# Carte_elec.net
KiCad netlist of a schematic drawn in EAGLE
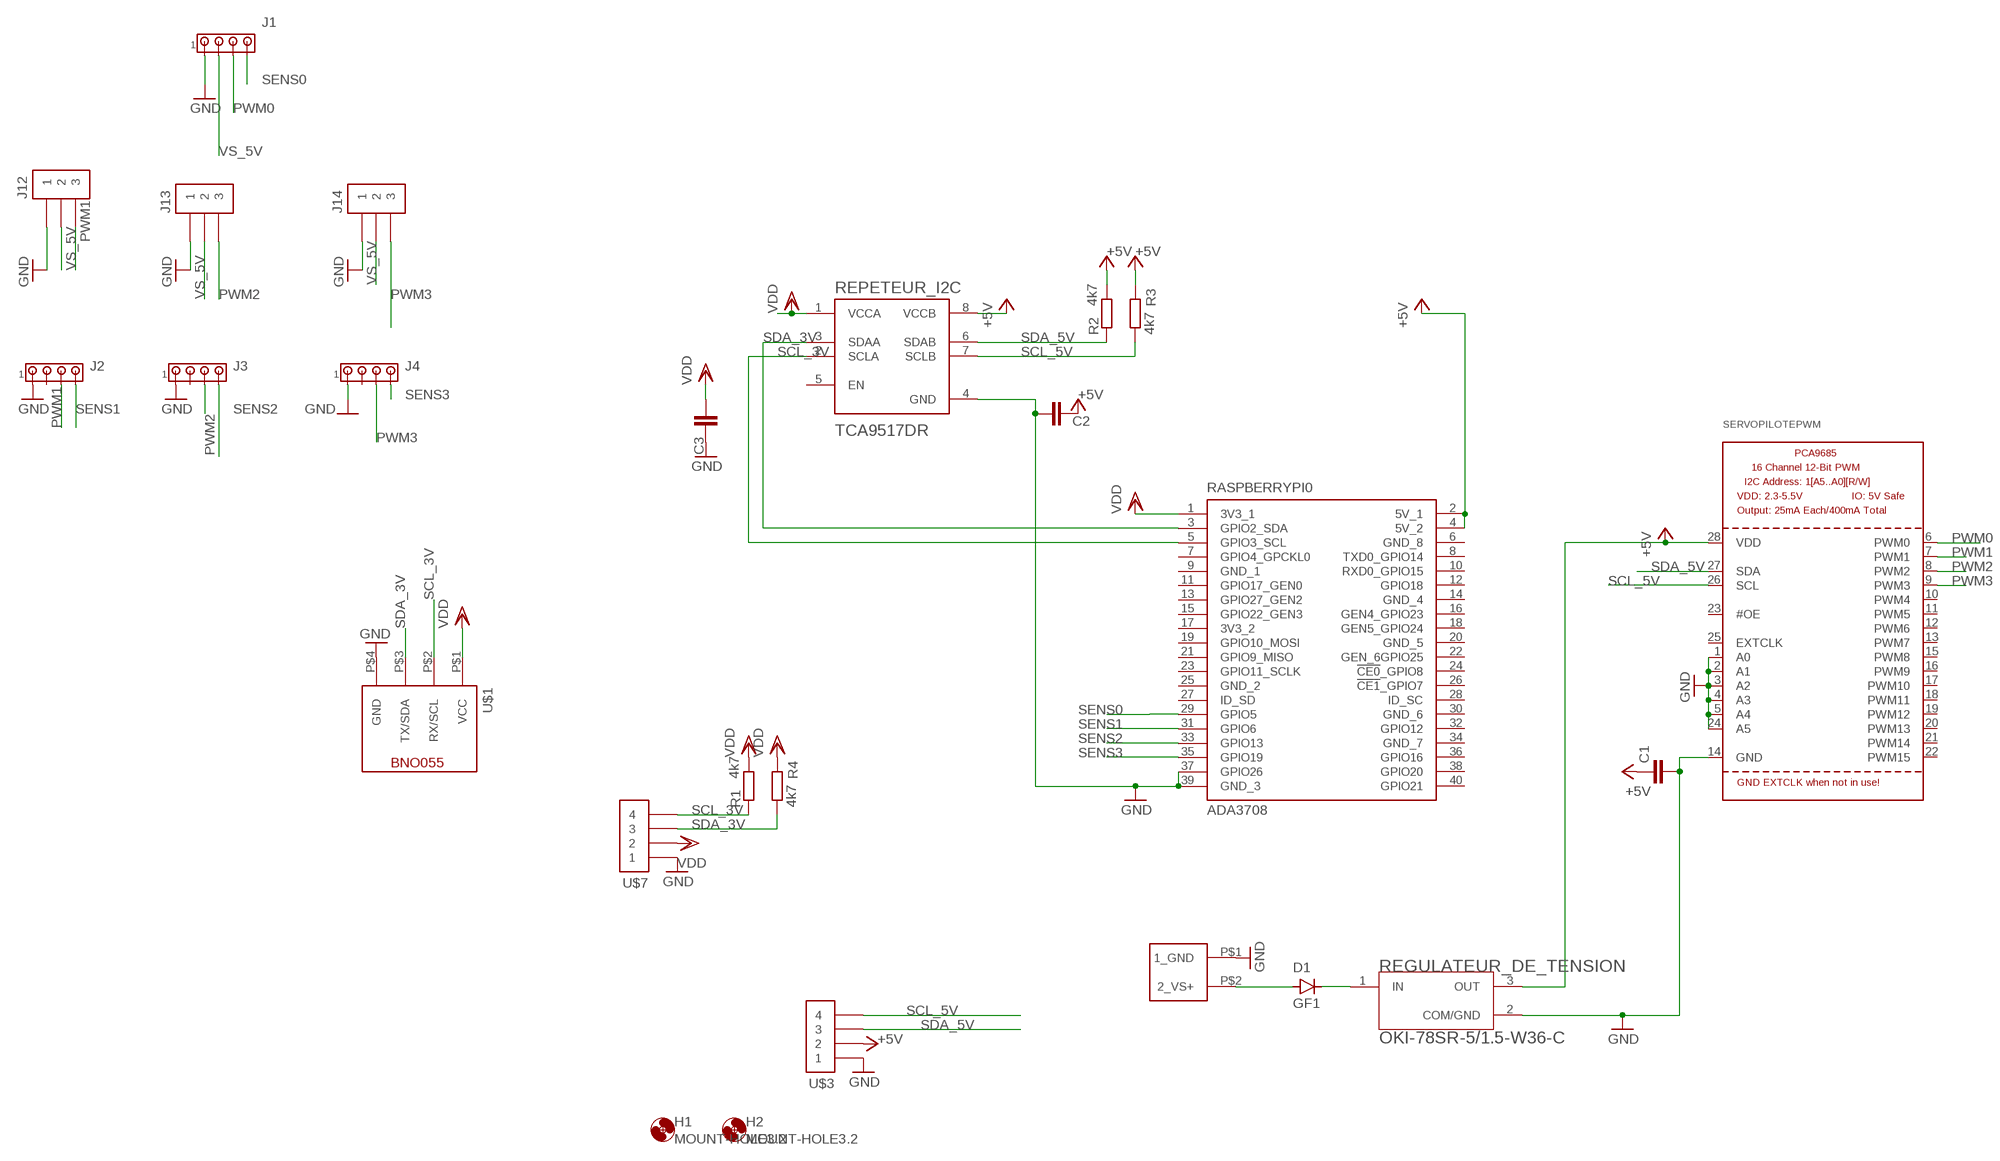
[diagram p0: schematic, sheet 1]

(export (version "E")
  (design (tool "Eeschema 10.0.6"))
  (components
    (comp (ref "C1")
      (value "C-EUC1206")
      (footprint "eagle-import:C1206")
      (libsource (lib "eagle-import") (part "C-EUC1206"))
    )
    (comp (ref "C2")
      (value "C-EUC1206")
      (footprint "eagle-import:C1206")
      (libsource (lib "eagle-import") (part "C-EUC1206"))
    )
    (comp (ref "C3")
      (value "C-EUC1206")
      (footprint "eagle-import:C1206")
      (libsource (lib "eagle-import") (part "C-EUC1206"))
    )
    (comp (ref "D1")
      (value "GF1")
      (footprint "eagle-import:SMA-DO214AC")
      (libsource (lib "eagle-import") (part "GF1"))
    )
    (comp (ref "H1")
      (value "MOUNT-HOLE3.2")
      (footprint "eagle-import:3,2")
      (libsource (lib "eagle-import") (part "MOUNT-HOLE3.2"))
    )
    (comp (ref "H2")
      (value "MOUNT-HOLE3.2")
      (footprint "eagle-import:3,2")
      (libsource (lib "eagle-import") (part "MOUNT-HOLE3.2"))
    )
    (comp (ref "J1")
      (value "MTA04-100")
      (footprint "eagle-import:10X04MTA")
      (libsource (lib "eagle-import") (part "MTA04-100"))
    )
    (comp (ref "J2")
      (value "MTA04-100")
      (footprint "eagle-import:10X04MTA")
      (libsource (lib "eagle-import") (part "MTA04-100"))
    )
    (comp (ref "J3")
      (value "MTA04-100")
      (footprint "eagle-import:10X04MTA")
      (libsource (lib "eagle-import") (part "MTA04-100"))
    )
    (comp (ref "J4")
      (value "MTA04-100")
      (footprint "eagle-import:10X04MTA")
      (libsource (lib "eagle-import") (part "MTA04-100"))
    )
    (comp (ref "J12")
      (value "CAVALIER_3")
      (footprint "eagle-import:CAVALIER_3")
      (libsource (lib "eagle-import") (part "CAVALIER_3"))
    )
    (comp (ref "J13")
      (value "CAVALIER_3")
      (footprint "eagle-import:CAVALIER_3")
      (libsource (lib "eagle-import") (part "CAVALIER_3"))
    )
    (comp (ref "J14")
      (value "CAVALIER_3")
      (footprint "eagle-import:CAVALIER_3")
      (libsource (lib "eagle-import") (part "CAVALIER_3"))
    )
    (comp (ref "R1")
      (value "4k7")
      (footprint "eagle-import:R1206")
      (libsource (lib "eagle-import") (part "R-EU_R1206"))
    )
    (comp (ref "R2")
      (value "4k7")
      (footprint "eagle-import:R1206")
      (libsource (lib "eagle-import") (part "R-EU_R1206"))
    )
    (comp (ref "R3")
      (value "4k7")
      (footprint "eagle-import:R1206")
      (libsource (lib "eagle-import") (part "R-EU_R1206"))
    )
    (comp (ref "R4")
      (value "4k7")
      (footprint "eagle-import:R1206")
      (libsource (lib "eagle-import") (part "R-EU_R1206"))
    )
    (comp (ref "RASPBERRYPI0")
      (value "ADA3708")
      (footprint "eagle-import:MODULE_ADA3708")
      (fields (field (name "MF") "Adafruit Industries"))
      (libsource (lib "eagle-import") (part "ADA3708"))
    )
    (comp (ref "REGULATEUR_DE_TENSION")
      (value "OKI-78SR-5/1.5-W36-C")
      (footprint "eagle-import:CONV_OKI-78SR-5_1.5-W36-C")
      (fields (field (name "MF") "Murata Power Solutions"))
      (libsource (lib "eagle-import") (part "OKI-78SR-5/1.5-W36-C"))
    )
    (comp (ref "REPETEUR_I2C")
      (value "TCA9517DR")
      (footprint "eagle-import:SOIC127P599X175-8N")
      (fields (field (name "MF") "Texas Instruments"))
      (libsource (lib "eagle-import") (part "TCA9517DR"))
    )
    (comp (ref "SERVOPILOTEPWM")
      (value "PCA9685")
      (footprint "eagle-import:TSSOP28")
      (libsource (lib "eagle-import") (part "PCA9685"))
    )
    (comp (ref "U$1")
      (value "MODULE_BNO055")
      (footprint "eagle-import:MODULE_BNO055")
      (libsource (lib "eagle-import") (part "MODULE_BNO055"))
    )
    (comp (ref "U$2")
      (value "CONN_ALIM")
      (footprint "eagle-import:CONN_ALIM")
      (libsource (lib "eagle-import") (part "CONN_ALIM"))
    )
    (comp (ref "U$3")
      (value "MOLEX_4_DROIT")
      (footprint "eagle-import:MOLEX_4_DROIT")
      (libsource (lib "eagle-import") (part "MOLEX_4_DROIT"))
    )
    (comp (ref "U$7")
      (value "MOLEX_4_DROIT")
      (footprint "eagle-import:MOLEX_4_DROIT")
      (libsource (lib "eagle-import") (part "MOLEX_4_DROIT"))
    )
  )
  (nets
    (net (code "1") (name "+5V") (class "Default")
      (node (ref "C1") (pin "1") (pinfunction "1_1") (pintype "passive"))
      (node (ref "C2") (pin "1") (pinfunction "1_1") (pintype "passive"))
      (node (ref "R2") (pin "2") (pinfunction "2_2") (pintype "passive"))
      (node (ref "R3") (pin "2") (pinfunction "2_2") (pintype "passive"))
      (node (ref "RASPBERRYPI0") (pin "2") (pinfunction "5V_1_2") (pintype "power_in"))
      (node (ref "RASPBERRYPI0") (pin "4") (pinfunction "5V_2_4") (pintype "power_in"))
      (node (ref "REGULATEUR_DE_TENSION") (pin "3") (pinfunction "OUT_3") (pintype "output"))
      (node (ref "REPETEUR_I2C") (pin "8") (pinfunction "VCCB_8") (pintype "power_in"))
      (node (ref "SERVOPILOTEPWM") (pin "28") (pinfunction "VDD_28") (pintype "power_in"))
      (node (ref "U$3") (pin "P$2") (pinfunction "2_P$2") (pintype "bidirectional"))
    )
    (net (code "2") (name "/3V3_2") (class "Default")
      (node (ref "RASPBERRYPI0") (pin "17") (pinfunction "3V3_2_17") (pintype "power_in"))
    )
    (net (code "3") (name "/GND_1") (class "Default")
      (node (ref "RASPBERRYPI0") (pin "9") (pinfunction "GND_1_9") (pintype "power_in"))
    )
    (net (code "4") (name "/GND_2") (class "Default")
      (node (ref "RASPBERRYPI0") (pin "25") (pinfunction "GND_2_25") (pintype "power_in"))
    )
    (net (code "5") (name "/GND_4") (class "Default")
      (node (ref "RASPBERRYPI0") (pin "14") (pinfunction "GND_4_14") (pintype "power_in"))
    )
    (net (code "6") (name "/GND_5") (class "Default")
      (node (ref "RASPBERRYPI0") (pin "20") (pinfunction "GND_5_20") (pintype "power_in"))
    )
    (net (code "7") (name "/GND_6") (class "Default")
      (node (ref "RASPBERRYPI0") (pin "30") (pinfunction "GND_6_30") (pintype "power_in"))
    )
    (net (code "8") (name "/GND_7") (class "Default")
      (node (ref "RASPBERRYPI0") (pin "34") (pinfunction "GND_7_34") (pintype "power_in"))
    )
    (net (code "9") (name "/GND_8") (class "Default")
      (node (ref "RASPBERRYPI0") (pin "6") (pinfunction "GND_8_6") (pintype "power_in"))
    )
    (net (code "10") (name "/PWM0") (class "Default")
      (node (ref "J1") (pin "3") (pinfunction "3_3") (pintype "passive"))
      (node (ref "SERVOPILOTEPWM") (pin "6") (pinfunction "PWM0_6") (pintype "output"))
    )
    (net (code "11") (name "/PWM1") (class "Default")
      (node (ref "J12") (pin "P$3") (pinfunction "3_P$3") (pintype "bidirectional"))
      (node (ref "J2") (pin "3") (pinfunction "3_3") (pintype "passive"))
      (node (ref "SERVOPILOTEPWM") (pin "7") (pinfunction "PWM1_7") (pintype "output"))
    )
    (net (code "12") (name "/PWM2") (class "Default")
      (node (ref "J13") (pin "P$3") (pinfunction "3_P$3") (pintype "bidirectional"))
      (node (ref "J3") (pin "3") (pinfunction "3_3") (pintype "passive"))
      (node (ref "SERVOPILOTEPWM") (pin "8") (pinfunction "PWM2_8") (pintype "output"))
    )
    (net (code "13") (name "/PWM3") (class "Default")
      (node (ref "J14") (pin "P$3") (pinfunction "3_P$3") (pintype "bidirectional"))
      (node (ref "J4") (pin "3") (pinfunction "3_3") (pintype "passive"))
      (node (ref "SERVOPILOTEPWM") (pin "9") (pinfunction "PWM3_9") (pintype "output"))
    )
    (net (code "14") (name "/SCL_3V") (class "Default")
      (node (ref "R1") (pin "1") (pinfunction "1_1") (pintype "passive"))
      (node (ref "RASPBERRYPI0") (pin "5") (pinfunction "GPIO3_SCL_5") (pintype "bidirectional"))
      (node (ref "REPETEUR_I2C") (pin "2") (pinfunction "SCLA_2") (pintype "bidirectional"))
      (node (ref "U$1") (pin "P$2") (pinfunction "RX/SCL_P$2") (pintype "bidirectional"))
      (node (ref "U$7") (pin "P$4") (pinfunction "4_P$4") (pintype "bidirectional"))
    )
    (net (code "15") (name "/SCL_5V") (class "Default")
      (node (ref "R3") (pin "1") (pinfunction "1_1") (pintype "passive"))
      (node (ref "REPETEUR_I2C") (pin "7") (pinfunction "SCLB_7") (pintype "bidirectional"))
      (node (ref "SERVOPILOTEPWM") (pin "26") (pinfunction "SCL_26") (pintype "bidirectional"))
      (node (ref "U$3") (pin "P$4") (pinfunction "4_P$4") (pintype "bidirectional"))
    )
    (net (code "16") (name "/SDA_3V") (class "Default")
      (node (ref "R4") (pin "1") (pinfunction "1_1") (pintype "passive"))
      (node (ref "RASPBERRYPI0") (pin "3") (pinfunction "GPIO2_SDA_3") (pintype "bidirectional"))
      (node (ref "REPETEUR_I2C") (pin "3") (pinfunction "SDAA_3") (pintype "bidirectional"))
      (node (ref "U$1") (pin "P$3") (pinfunction "TX/SDA_P$3") (pintype "bidirectional"))
      (node (ref "U$7") (pin "P$3") (pinfunction "3_P$3") (pintype "bidirectional"))
    )
    (net (code "17") (name "/SDA_5V") (class "Default")
      (node (ref "R2") (pin "1") (pinfunction "1_1") (pintype "passive"))
      (node (ref "REPETEUR_I2C") (pin "6") (pinfunction "SDAB_6") (pintype "bidirectional"))
      (node (ref "SERVOPILOTEPWM") (pin "27") (pinfunction "SDA_27") (pintype "bidirectional"))
      (node (ref "U$3") (pin "P$3") (pinfunction "3_P$3") (pintype "bidirectional"))
    )
    (net (code "18") (name "/SENS0") (class "Default")
      (node (ref "J1") (pin "4") (pinfunction "4_4") (pintype "passive"))
      (node (ref "RASPBERRYPI0") (pin "29") (pinfunction "GPIO5_29") (pintype "bidirectional"))
    )
    (net (code "19") (name "/SENS1") (class "Default")
      (node (ref "J2") (pin "4") (pinfunction "4_4") (pintype "passive"))
      (node (ref "RASPBERRYPI0") (pin "31") (pinfunction "GPIO6_31") (pintype "bidirectional"))
    )
    (net (code "20") (name "/SENS2") (class "Default")
      (node (ref "J3") (pin "4") (pinfunction "4_4") (pintype "passive"))
      (node (ref "RASPBERRYPI0") (pin "33") (pinfunction "GPIO13_33") (pintype "bidirectional"))
    )
    (net (code "21") (name "/SENS3") (class "Default")
      (node (ref "J4") (pin "4") (pinfunction "4_4") (pintype "passive"))
      (node (ref "RASPBERRYPI0") (pin "35") (pinfunction "GPIO19_35") (pintype "bidirectional"))
    )
    (net (code "22") (name "/VS_5V") (class "Default")
      (node (ref "J1") (pin "2") (pinfunction "2_2") (pintype "passive"))
      (node (ref "J12") (pin "P$2") (pinfunction "2_P$2") (pintype "bidirectional"))
      (node (ref "J14") (pin "P$2") (pinfunction "2_P$2") (pintype "bidirectional"))
    )
    (net (code "23") (name "GND") (class "Default")
      (node (ref "C1") (pin "2") (pinfunction "2_2") (pintype "passive"))
      (node (ref "C2") (pin "2") (pinfunction "2_2") (pintype "passive"))
      (node (ref "C3") (pin "1") (pinfunction "1_1") (pintype "passive"))
      (node (ref "J1") (pin "1") (pinfunction "1_1") (pintype "passive"))
      (node (ref "J12") (pin "P$1") (pinfunction "1_P$1") (pintype "bidirectional"))
      (node (ref "J13") (pin "P$1") (pinfunction "1_P$1") (pintype "bidirectional"))
      (node (ref "J14") (pin "P$1") (pinfunction "1_P$1") (pintype "bidirectional"))
      (node (ref "J2") (pin "1") (pinfunction "1_1") (pintype "passive"))
      (node (ref "J3") (pin "1") (pinfunction "1_1") (pintype "passive"))
      (node (ref "J4") (pin "1") (pinfunction "1_1") (pintype "passive"))
      (node (ref "RASPBERRYPI0") (pin "37") (pinfunction "GPIO26_37") (pintype "bidirectional"))
      (node (ref "RASPBERRYPI0") (pin "39") (pinfunction "GND_3_39") (pintype "power_in"))
      (node (ref "REGULATEUR_DE_TENSION") (pin "2") (pinfunction "COM/GND_2") (pintype "power_in"))
      (node (ref "REPETEUR_I2C") (pin "4") (pinfunction "GND_4") (pintype "power_in"))
      (node (ref "SERVOPILOTEPWM") (pin "1") (pinfunction "A0_1") (pintype "bidirectional"))
      (node (ref "SERVOPILOTEPWM") (pin "14") (pinfunction "GND_14") (pintype "power_in"))
      (node (ref "SERVOPILOTEPWM") (pin "2") (pinfunction "A1_2") (pintype "bidirectional"))
      (node (ref "SERVOPILOTEPWM") (pin "24") (pinfunction "A5_24") (pintype "bidirectional"))
      (node (ref "SERVOPILOTEPWM") (pin "3") (pinfunction "A2_3") (pintype "bidirectional"))
      (node (ref "SERVOPILOTEPWM") (pin "4") (pinfunction "A3_4") (pintype "bidirectional"))
      (node (ref "SERVOPILOTEPWM") (pin "5") (pinfunction "A4_5") (pintype "bidirectional"))
      (node (ref "U$1") (pin "P$4") (pinfunction "GND_P$4") (pintype "bidirectional"))
      (node (ref "U$2") (pin "P$1") (pinfunction "1_GND_P$1") (pintype "bidirectional"))
      (node (ref "U$3") (pin "P$1") (pinfunction "1_P$1") (pintype "bidirectional"))
      (node (ref "U$7") (pin "P$1") (pinfunction "1_P$1") (pintype "bidirectional"))
    )
    (net (code "24") (name "Net-(D1-C)") (class "Default")
      (node (ref "D1") (pin "K") (pinfunction "C_K") (pintype "passive"))
      (node (ref "REGULATEUR_DE_TENSION") (pin "1") (pinfunction "IN_1") (pintype "input"))
    )
    (net (code "25") (name "Net-(U$2-2_VS+)") (class "Default")
      (node (ref "D1") (pin "A") (pinfunction "A_A") (pintype "passive"))
      (node (ref "U$2") (pin "P$2") (pinfunction "2_VS+_P$2") (pintype "bidirectional"))
    )
    (net (code "26") (name "VDD") (class "Default")
      (node (ref "C3") (pin "2") (pinfunction "2_2") (pintype "passive"))
      (node (ref "R1") (pin "2") (pinfunction "2_2") (pintype "passive"))
      (node (ref "R4") (pin "2") (pinfunction "2_2") (pintype "passive"))
      (node (ref "RASPBERRYPI0") (pin "1") (pinfunction "3V3_1_1") (pintype "power_in"))
      (node (ref "REPETEUR_I2C") (pin "1") (pinfunction "VCCA_1") (pintype "power_in"))
      (node (ref "U$1") (pin "P$1") (pinfunction "VCC_P$1") (pintype "bidirectional"))
      (node (ref "U$7") (pin "P$2") (pinfunction "2_P$2") (pintype "bidirectional"))
    )
    (net (code "27") (name "unconnected-(J2-Pad2)") (class "Default")
      (node (ref "J2") (pin "2") (pinfunction "2_2") (pintype "passive"))
    )
    (net (code "28") (name "unconnected-(J3-Pad2)") (class "Default")
      (node (ref "J3") (pin "2") (pinfunction "2_2") (pintype "passive"))
    )
    (net (code "29") (name "unconnected-(J4-Pad2)") (class "Default")
      (node (ref "J4") (pin "2") (pinfunction "2_2") (pintype "passive"))
    )
    (net (code "30") (name "unconnected-(J13-2-PadP$2)") (class "Default")
      (node (ref "J13") (pin "P$2") (pinfunction "2_P$2") (pintype "bidirectional"))
    )
    (net (code "31") (name "unconnected-(RASPBERRYPI0-GEN4_GPIO23-Pad16)") (class "Default")
      (node (ref "RASPBERRYPI0") (pin "16") (pinfunction "GEN4_GPIO23_16") (pintype "bidirectional"))
    )
    (net (code "32") (name "unconnected-(RASPBERRYPI0-GEN5_GPIO24-Pad18)") (class "Default")
      (node (ref "RASPBERRYPI0") (pin "18") (pinfunction "GEN5_GPIO24_18") (pintype "bidirectional"))
    )
    (net (code "33") (name "unconnected-(RASPBERRYPI0-GEN_6GPIO25-Pad22)") (class "Default")
      (node (ref "RASPBERRYPI0") (pin "22") (pinfunction "GEN_6GPIO25_22") (pintype "bidirectional"))
    )
    (net (code "34") (name "unconnected-(RASPBERRYPI0-GPIO4_GPCKL0-Pad7)") (class "Default")
      (node (ref "RASPBERRYPI0") (pin "7") (pinfunction "GPIO4_GPCKL0_7") (pintype "bidirectional"))
    )
    (net (code "35") (name "unconnected-(RASPBERRYPI0-GPIO9_MISO-Pad21)") (class "Default")
      (node (ref "RASPBERRYPI0") (pin "21") (pinfunction "GPIO9_MISO_21") (pintype "bidirectional"))
    )
    (net (code "36") (name "unconnected-(RASPBERRYPI0-GPIO10_MOSI-Pad19)") (class "Default")
      (node (ref "RASPBERRYPI0") (pin "19") (pinfunction "GPIO10_MOSI_19") (pintype "bidirectional"))
    )
    (net (code "37") (name "unconnected-(RASPBERRYPI0-GPIO11_SCLK-Pad23)") (class "Default")
      (node (ref "RASPBERRYPI0") (pin "23") (pinfunction "GPIO11_SCLK_23") (pintype "bidirectional"))
    )
    (net (code "38") (name "unconnected-(RASPBERRYPI0-GPIO12-Pad32)") (class "Default")
      (node (ref "RASPBERRYPI0") (pin "32") (pinfunction "GPIO12_32") (pintype "bidirectional"))
    )
    (net (code "39") (name "unconnected-(RASPBERRYPI0-GPIO16-Pad36)") (class "Default")
      (node (ref "RASPBERRYPI0") (pin "36") (pinfunction "GPIO16_36") (pintype "bidirectional"))
    )
    (net (code "40") (name "unconnected-(RASPBERRYPI0-GPIO17_GEN0-Pad11)") (class "Default")
      (node (ref "RASPBERRYPI0") (pin "11") (pinfunction "GPIO17_GEN0_11") (pintype "bidirectional"))
    )
    (net (code "41") (name "unconnected-(RASPBERRYPI0-GPIO18-Pad12)") (class "Default")
      (node (ref "RASPBERRYPI0") (pin "12") (pinfunction "GPIO18_12") (pintype "bidirectional"))
    )
    (net (code "42") (name "unconnected-(RASPBERRYPI0-GPIO20-Pad38)") (class "Default")
      (node (ref "RASPBERRYPI0") (pin "38") (pinfunction "GPIO20_38") (pintype "bidirectional"))
    )
    (net (code "43") (name "unconnected-(RASPBERRYPI0-GPIO21-Pad40)") (class "Default")
      (node (ref "RASPBERRYPI0") (pin "40") (pinfunction "GPIO21_40") (pintype "bidirectional"))
    )
    (net (code "44") (name "unconnected-(RASPBERRYPI0-GPIO22_GEN3-Pad15)") (class "Default")
      (node (ref "RASPBERRYPI0") (pin "15") (pinfunction "GPIO22_GEN3_15") (pintype "bidirectional"))
    )
    (net (code "45") (name "unconnected-(RASPBERRYPI0-GPIO27_GEN2-Pad13)") (class "Default")
      (node (ref "RASPBERRYPI0") (pin "13") (pinfunction "GPIO27_GEN2_13") (pintype "bidirectional"))
    )
    (net (code "46") (name "unconnected-(RASPBERRYPI0-ID_SC-Pad28)") (class "Default")
      (node (ref "RASPBERRYPI0") (pin "28") (pinfunction "ID_SC_28") (pintype "bidirectional"))
    )
    (net (code "47") (name "unconnected-(RASPBERRYPI0-ID_SD-Pad27)") (class "Default")
      (node (ref "RASPBERRYPI0") (pin "27") (pinfunction "ID_SD_27") (pintype "bidirectional"))
    )
    (net (code "48") (name "unconnected-(RASPBERRYPI0-RXD0_GPIO15-Pad10)") (class "Default")
      (node (ref "RASPBERRYPI0") (pin "10") (pinfunction "RXD0_GPIO15_10") (pintype "bidirectional"))
    )
    (net (code "49") (name "unconnected-(RASPBERRYPI0-TXD0_GPIO14-Pad8)") (class "Default")
      (node (ref "RASPBERRYPI0") (pin "8") (pinfunction "TXD0_GPIO14_8") (pintype "bidirectional"))
    )
    (net (code "50") (name "unconnected-(RASPBERRYPI0-~{CE0}_GPIO8-Pad24)") (class "Default")
      (node (ref "RASPBERRYPI0") (pin "24") (pinfunction "~{CE0}_GPIO8_24") (pintype "bidirectional"))
    )
    (net (code "51") (name "unconnected-(RASPBERRYPI0-~{CE1}_GPIO7-Pad26)") (class "Default")
      (node (ref "RASPBERRYPI0") (pin "26") (pinfunction "~{CE1}_GPIO7_26") (pintype "bidirectional"))
    )
    (net (code "52") (name "unconnected-(REPETEUR_I2C-EN-Pad5)") (class "Default")
      (node (ref "REPETEUR_I2C") (pin "5") (pinfunction "EN_5") (pintype "input"))
    )
    (net (code "53") (name "unconnected-(SERVOPILOTEPWM-#OE-Pad23)") (class "Default")
      (node (ref "SERVOPILOTEPWM") (pin "23") (pinfunction "#OE_23") (pintype "input"))
    )
    (net (code "54") (name "unconnected-(SERVOPILOTEPWM-EXTCLK-Pad25)") (class "Default")
      (node (ref "SERVOPILOTEPWM") (pin "25") (pinfunction "EXTCLK_25") (pintype "input"))
    )
    (net (code "55") (name "unconnected-(SERVOPILOTEPWM-PWM4-Pad10)") (class "Default")
      (node (ref "SERVOPILOTEPWM") (pin "10") (pinfunction "PWM4_10") (pintype "output"))
    )
    (net (code "56") (name "unconnected-(SERVOPILOTEPWM-PWM5-Pad11)") (class "Default")
      (node (ref "SERVOPILOTEPWM") (pin "11") (pinfunction "PWM5_11") (pintype "output"))
    )
    (net (code "57") (name "unconnected-(SERVOPILOTEPWM-PWM6-Pad12)") (class "Default")
      (node (ref "SERVOPILOTEPWM") (pin "12") (pinfunction "PWM6_12") (pintype "output"))
    )
    (net (code "58") (name "unconnected-(SERVOPILOTEPWM-PWM7-Pad13)") (class "Default")
      (node (ref "SERVOPILOTEPWM") (pin "13") (pinfunction "PWM7_13") (pintype "output"))
    )
    (net (code "59") (name "unconnected-(SERVOPILOTEPWM-PWM8-Pad15)") (class "Default")
      (node (ref "SERVOPILOTEPWM") (pin "15") (pinfunction "PWM8_15") (pintype "output"))
    )
    (net (code "60") (name "unconnected-(SERVOPILOTEPWM-PWM9-Pad16)") (class "Default")
      (node (ref "SERVOPILOTEPWM") (pin "16") (pinfunction "PWM9_16") (pintype "output"))
    )
    (net (code "61") (name "unconnected-(SERVOPILOTEPWM-PWM10-Pad17)") (class "Default")
      (node (ref "SERVOPILOTEPWM") (pin "17") (pinfunction "PWM10_17") (pintype "output"))
    )
    (net (code "62") (name "unconnected-(SERVOPILOTEPWM-PWM11-Pad18)") (class "Default")
      (node (ref "SERVOPILOTEPWM") (pin "18") (pinfunction "PWM11_18") (pintype "output"))
    )
    (net (code "63") (name "unconnected-(SERVOPILOTEPWM-PWM12-Pad19)") (class "Default")
      (node (ref "SERVOPILOTEPWM") (pin "19") (pinfunction "PWM12_19") (pintype "output"))
    )
    (net (code "64") (name "unconnected-(SERVOPILOTEPWM-PWM13-Pad20)") (class "Default")
      (node (ref "SERVOPILOTEPWM") (pin "20") (pinfunction "PWM13_20") (pintype "output"))
    )
    (net (code "65") (name "unconnected-(SERVOPILOTEPWM-PWM14-Pad21)") (class "Default")
      (node (ref "SERVOPILOTEPWM") (pin "21") (pinfunction "PWM14_21") (pintype "output"))
    )
    (net (code "66") (name "unconnected-(SERVOPILOTEPWM-PWM15-Pad22)") (class "Default")
      (node (ref "SERVOPILOTEPWM") (pin "22") (pinfunction "PWM15_22") (pintype "output"))
    )
  )
)
